# schematic.net
KiCad netlist of a schematic drawn in EAGLE
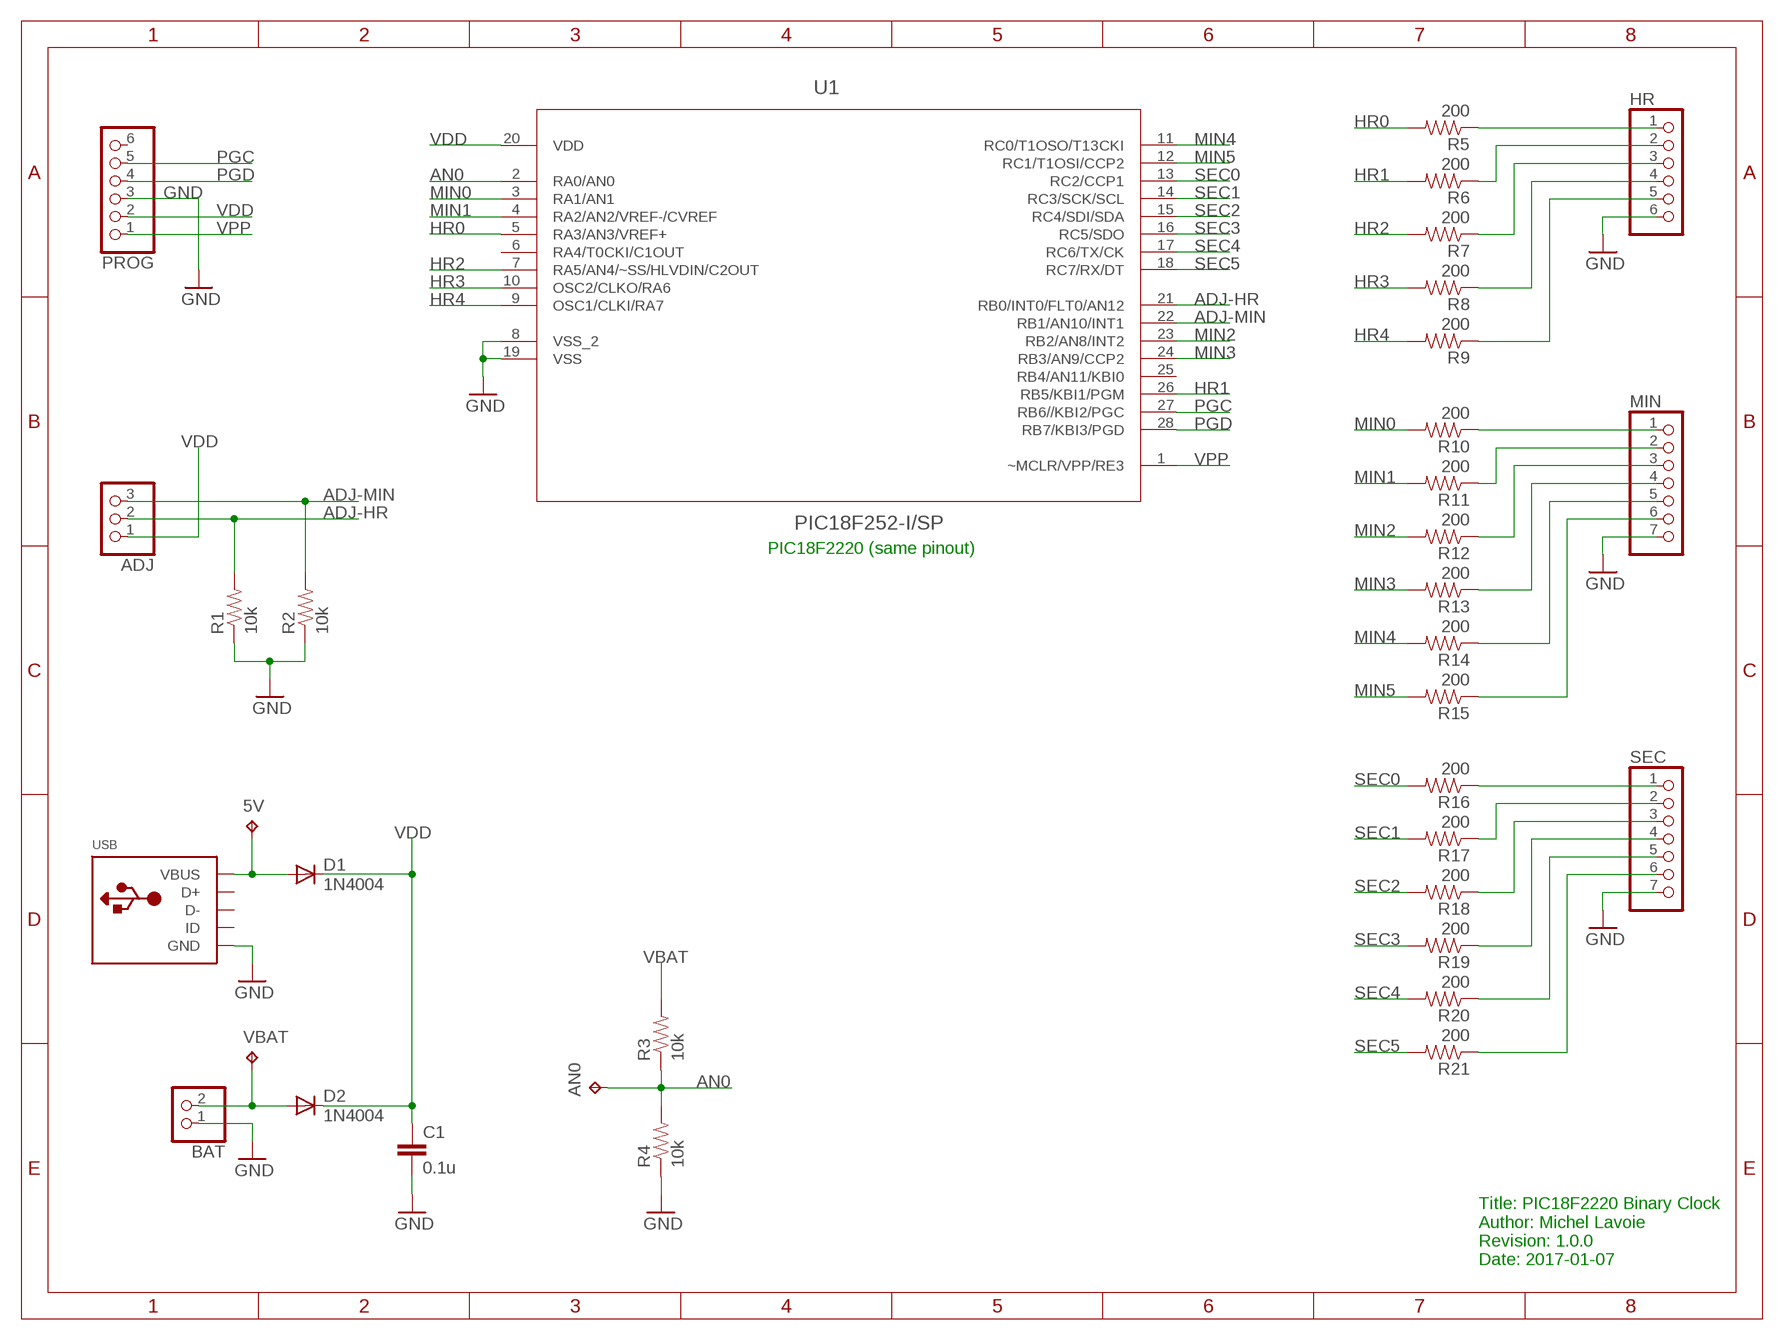
[diagram p0: schematic, sheet 1]

(export (version "E")
  (design (tool "Eeschema 10.0.6"))
  (components
    (comp (ref "5V")
      (value "TPPAD1-13")
      (footprint "eagle-import:P1-13")
      (libsource (lib "eagle-import") (part "TPPAD1-13"))
    )
    (comp (ref "ADJ")
      (value "PINHD-1X3")
      (footprint "eagle-import:1X03")
      (libsource (lib "eagle-import") (part "PINHD-1X3"))
    )
    (comp (ref "AN0")
      (value "TPPAD1-13")
      (footprint "eagle-import:P1-13")
      (libsource (lib "eagle-import") (part "TPPAD1-13"))
    )
    (comp (ref "BAT")
      (value "PINHD-1X2")
      (footprint "eagle-import:1X02")
      (libsource (lib "eagle-import") (part "PINHD-1X2"))
    )
    (comp (ref "C1")
      (value "0.1u")
      (footprint "eagle-import:CAP-PTH-SMALL-KIT")
      (libsource (lib "eagle-import") (part "0.1UF-50V-20%(PTH)KIT-EZ"))
    )
    (comp (ref "D1")
      (value "1N4004")
      (footprint "eagle-import:DO41-10")
      (libsource (lib "eagle-import") (part "1N4004"))
    )
    (comp (ref "D2")
      (value "1N4004")
      (footprint "eagle-import:DO41-10")
      (libsource (lib "eagle-import") (part "1N4004"))
    )
    (comp (ref "HR")
      (value "PINHD-1X6")
      (footprint "eagle-import:1X06")
      (libsource (lib "eagle-import") (part "PINHD-1X6"))
    )
    (comp (ref "MIN")
      (value "PINHD-1X7")
      (footprint "eagle-import:1X07")
      (libsource (lib "eagle-import") (part "PINHD-1X7"))
    )
    (comp (ref "PROG")
      (value "PINHD-1X6")
      (footprint "eagle-import:1X06")
      (libsource (lib "eagle-import") (part "PINHD-1X6"))
    )
    (comp (ref "R1")
      (value "10k")
      (footprint "eagle-import:AXIAL-0.3")
      (libsource (lib "eagle-import") (part "10KOHM-1/4W5%(PTH)"))
    )
    (comp (ref "R2")
      (value "10k")
      (footprint "eagle-import:AXIAL-0.3")
      (libsource (lib "eagle-import") (part "10KOHM-1/4W5%(PTH)"))
    )
    (comp (ref "R3")
      (value "10k")
      (footprint "eagle-import:AXIAL-0.3")
      (libsource (lib "eagle-import") (part "10KOHM-1/4W5%(PTH)"))
    )
    (comp (ref "R4")
      (value "10k")
      (footprint "eagle-import:AXIAL-0.3")
      (libsource (lib "eagle-import") (part "10KOHM-1/4W5%(PTH)"))
    )
    (comp (ref "R5")
      (value "200")
      (footprint "eagle-import:AXIAL-0.3")
      (libsource (lib "eagle-import") (part "10KOHM-1/4W5%(PTH)"))
    )
    (comp (ref "R6")
      (value "200")
      (footprint "eagle-import:AXIAL-0.3")
      (libsource (lib "eagle-import") (part "10KOHM-1/4W5%(PTH)"))
    )
    (comp (ref "R7")
      (value "200")
      (footprint "eagle-import:AXIAL-0.3")
      (libsource (lib "eagle-import") (part "10KOHM-1/4W5%(PTH)"))
    )
    (comp (ref "R8")
      (value "200")
      (footprint "eagle-import:AXIAL-0.3")
      (libsource (lib "eagle-import") (part "10KOHM-1/4W5%(PTH)"))
    )
    (comp (ref "R9")
      (value "200")
      (footprint "eagle-import:AXIAL-0.3")
      (libsource (lib "eagle-import") (part "10KOHM-1/4W5%(PTH)"))
    )
    (comp (ref "R10")
      (value "200")
      (footprint "eagle-import:AXIAL-0.3")
      (libsource (lib "eagle-import") (part "10KOHM-1/4W5%(PTH)"))
    )
    (comp (ref "R11")
      (value "200")
      (footprint "eagle-import:AXIAL-0.3")
      (libsource (lib "eagle-import") (part "10KOHM-1/4W5%(PTH)"))
    )
    (comp (ref "R12")
      (value "200")
      (footprint "eagle-import:AXIAL-0.3")
      (libsource (lib "eagle-import") (part "10KOHM-1/4W5%(PTH)"))
    )
    (comp (ref "R13")
      (value "200")
      (footprint "eagle-import:AXIAL-0.3")
      (libsource (lib "eagle-import") (part "10KOHM-1/4W5%(PTH)"))
    )
    (comp (ref "R14")
      (value "200")
      (footprint "eagle-import:AXIAL-0.3")
      (libsource (lib "eagle-import") (part "10KOHM-1/4W5%(PTH)"))
    )
    (comp (ref "R15")
      (value "200")
      (footprint "eagle-import:AXIAL-0.3")
      (libsource (lib "eagle-import") (part "10KOHM-1/4W5%(PTH)"))
    )
    (comp (ref "R16")
      (value "200")
      (footprint "eagle-import:AXIAL-0.3")
      (libsource (lib "eagle-import") (part "10KOHM-1/4W5%(PTH)"))
    )
    (comp (ref "R17")
      (value "200")
      (footprint "eagle-import:AXIAL-0.3")
      (libsource (lib "eagle-import") (part "10KOHM-1/4W5%(PTH)"))
    )
    (comp (ref "R18")
      (value "200")
      (footprint "eagle-import:AXIAL-0.3")
      (libsource (lib "eagle-import") (part "10KOHM-1/4W5%(PTH)"))
    )
    (comp (ref "R19")
      (value "200")
      (footprint "eagle-import:AXIAL-0.3")
      (libsource (lib "eagle-import") (part "10KOHM-1/4W5%(PTH)"))
    )
    (comp (ref "R20")
      (value "200")
      (footprint "eagle-import:AXIAL-0.3")
      (libsource (lib "eagle-import") (part "10KOHM-1/4W5%(PTH)"))
    )
    (comp (ref "R21")
      (value "200")
      (footprint "eagle-import:AXIAL-0.3")
      (libsource (lib "eagle-import") (part "10KOHM-1/4W5%(PTH)"))
    )
    (comp (ref "SEC")
      (value "PINHD-1X7")
      (footprint "eagle-import:1X07")
      (libsource (lib "eagle-import") (part "PINHD-1X7"))
    )
    (comp (ref "U1")
      (value "PIC18F252-I/SP")
      (footprint "eagle-import:DIP254P762X508-28")
      (libsource (lib "eagle-import") (part "PIC18F252-I/SP"))
    )
    (comp (ref "USB")
      (value "USBTHM")
      (footprint "eagle-import:USB-MINIB-THM")
      (libsource (lib "eagle-import") (part "USBTHM"))
    )
    (comp (ref "VBAT")
      (value "TPPAD1-13")
      (footprint "eagle-import:P1-13")
      (libsource (lib "eagle-import") (part "TPPAD1-13"))
    )
  )
  (nets
    (net (code "1") (name "/ADJ-HR") (class "Default")
      (node (ref "ADJ") (pin "2") (pinfunction "2_2") (pintype "passive"))
      (node (ref "R1") (pin "P$2") (pinfunction "2_P$2") (pintype "passive"))
      (node (ref "U1") (pin "21") (pinfunction "RB0/INT0/FLT0/AN12_21") (pintype "bidirectional"))
    )
    (net (code "2") (name "/ADJ-MIN") (class "Default")
      (node (ref "ADJ") (pin "3") (pinfunction "3_3") (pintype "passive"))
      (node (ref "R2") (pin "P$2") (pinfunction "2_P$2") (pintype "passive"))
      (node (ref "U1") (pin "22") (pinfunction "RB1/AN10/INT1_22") (pintype "bidirectional"))
    )
    (net (code "3") (name "/AN0") (class "Default")
      (node (ref "AN0") (pin "TP") (pinfunction "TP_TP") (pintype "input"))
      (node (ref "R3") (pin "P$1") (pinfunction "1_P$1") (pintype "passive"))
      (node (ref "R4") (pin "P$2") (pinfunction "2_P$2") (pintype "passive"))
      (node (ref "U1") (pin "2") (pinfunction "RA0/AN0_2") (pintype "bidirectional"))
    )
    (net (code "4") (name "/HR0") (class "Default")
      (node (ref "R5") (pin "P$2") (pinfunction "2_P$2") (pintype "passive"))
      (node (ref "U1") (pin "5") (pinfunction "RA3/AN3/VREF+_5") (pintype "bidirectional"))
    )
    (net (code "5") (name "/HR1") (class "Default")
      (node (ref "R6") (pin "P$2") (pinfunction "2_P$2") (pintype "passive"))
      (node (ref "U1") (pin "26") (pinfunction "RB5/KBI1/PGM_26") (pintype "bidirectional"))
    )
    (net (code "6") (name "/HR2") (class "Default")
      (node (ref "R7") (pin "P$2") (pinfunction "2_P$2") (pintype "passive"))
      (node (ref "U1") (pin "7") (pinfunction "RA5/AN4/~{SS/HLVDIN/C2OUT}_7") (pintype "bidirectional"))
    )
    (net (code "7") (name "/HR3") (class "Default")
      (node (ref "R8") (pin "P$2") (pinfunction "2_P$2") (pintype "passive"))
      (node (ref "U1") (pin "10") (pinfunction "OSC2/CLKO/RA6_10") (pintype "bidirectional"))
    )
    (net (code "8") (name "/HR4") (class "Default")
      (node (ref "R9") (pin "P$2") (pinfunction "2_P$2") (pintype "passive"))
      (node (ref "U1") (pin "9") (pinfunction "OSC1/CLKI/RA7_9") (pintype "bidirectional"))
    )
    (net (code "9") (name "/MIN0") (class "Default")
      (node (ref "R10") (pin "P$2") (pinfunction "2_P$2") (pintype "passive"))
      (node (ref "U1") (pin "3") (pinfunction "RA1/AN1_3") (pintype "bidirectional"))
    )
    (net (code "10") (name "/MIN1") (class "Default")
      (node (ref "R11") (pin "P$2") (pinfunction "2_P$2") (pintype "passive"))
      (node (ref "U1") (pin "4") (pinfunction "RA2/AN2/VREF-/CVREF_4") (pintype "bidirectional"))
    )
    (net (code "11") (name "/MIN2") (class "Default")
      (node (ref "R12") (pin "P$2") (pinfunction "2_P$2") (pintype "passive"))
      (node (ref "U1") (pin "23") (pinfunction "RB2/AN8/INT2_23") (pintype "bidirectional"))
    )
    (net (code "12") (name "/MIN3") (class "Default")
      (node (ref "R13") (pin "P$2") (pinfunction "2_P$2") (pintype "passive"))
      (node (ref "U1") (pin "24") (pinfunction "RB3/AN9/CCP2_24") (pintype "bidirectional"))
    )
    (net (code "13") (name "/MIN4") (class "Default")
      (node (ref "R14") (pin "P$2") (pinfunction "2_P$2") (pintype "passive"))
      (node (ref "U1") (pin "11") (pinfunction "RC0/T1OSO/T13CKI_11") (pintype "bidirectional"))
    )
    (net (code "14") (name "/MIN5") (class "Default")
      (node (ref "R15") (pin "P$2") (pinfunction "2_P$2") (pintype "passive"))
      (node (ref "U1") (pin "12") (pinfunction "RC1/T1OSI/CCP2_12") (pintype "bidirectional"))
    )
    (net (code "15") (name "/PGC") (class "Default")
      (node (ref "PROG") (pin "5") (pinfunction "5_5") (pintype "passive"))
      (node (ref "U1") (pin "27") (pinfunction "RB6//KBI2/PGC_27") (pintype "bidirectional"))
    )
    (net (code "16") (name "/PGD") (class "Default")
      (node (ref "PROG") (pin "4") (pinfunction "4_4") (pintype "passive"))
      (node (ref "U1") (pin "28") (pinfunction "RB7/KBI3/PGD_28") (pintype "bidirectional"))
    )
    (net (code "17") (name "/SEC0") (class "Default")
      (node (ref "R16") (pin "P$2") (pinfunction "2_P$2") (pintype "passive"))
      (node (ref "U1") (pin "13") (pinfunction "RC2/CCP1_13") (pintype "bidirectional"))
    )
    (net (code "18") (name "/SEC1") (class "Default")
      (node (ref "R17") (pin "P$2") (pinfunction "2_P$2") (pintype "passive"))
      (node (ref "U1") (pin "14") (pinfunction "RC3/SCK/SCL_14") (pintype "bidirectional"))
    )
    (net (code "19") (name "/SEC2") (class "Default")
      (node (ref "R18") (pin "P$2") (pinfunction "2_P$2") (pintype "passive"))
      (node (ref "U1") (pin "15") (pinfunction "RC4/SDI/SDA_15") (pintype "bidirectional"))
    )
    (net (code "20") (name "/SEC3") (class "Default")
      (node (ref "R19") (pin "P$2") (pinfunction "2_P$2") (pintype "passive"))
      (node (ref "U1") (pin "16") (pinfunction "RC5/SDO_16") (pintype "bidirectional"))
    )
    (net (code "21") (name "/SEC4") (class "Default")
      (node (ref "R20") (pin "P$2") (pinfunction "2_P$2") (pintype "passive"))
      (node (ref "U1") (pin "17") (pinfunction "RC6/TX/CK_17") (pintype "bidirectional"))
    )
    (net (code "22") (name "/SEC5") (class "Default")
      (node (ref "R21") (pin "P$2") (pinfunction "2_P$2") (pintype "passive"))
      (node (ref "U1") (pin "18") (pinfunction "RC7/RX/DT_18") (pintype "bidirectional"))
    )
    (net (code "23") (name "/VBAT") (class "Default")
      (node (ref "BAT") (pin "2") (pinfunction "2_2") (pintype "passive"))
      (node (ref "D2") (pin "A") (pinfunction "A_A") (pintype "passive"))
      (node (ref "R3") (pin "P$2") (pinfunction "2_P$2") (pintype "passive"))
      (node (ref "VBAT") (pin "TP") (pinfunction "TP_TP") (pintype "input"))
    )
    (net (code "24") (name "/VDD") (class "Default")
      (node (ref "ADJ") (pin "1") (pinfunction "1_1") (pintype "passive"))
      (node (ref "C1") (pin "1") (pinfunction "1_1") (pintype "passive"))
      (node (ref "D1") (pin "C") (pinfunction "C_C") (pintype "passive"))
      (node (ref "D2") (pin "C") (pinfunction "C_C") (pintype "passive"))
      (node (ref "PROG") (pin "2") (pinfunction "2_2") (pintype "passive"))
      (node (ref "U1") (pin "20") (pinfunction "VDD_20") (pintype "power_in"))
    )
    (net (code "25") (name "/VPP") (class "Default")
      (node (ref "PROG") (pin "1") (pinfunction "1_1") (pintype "passive"))
      (node (ref "U1") (pin "1") (pinfunction "~{MCLR/VPP/RE3}_1") (pintype "bidirectional"))
    )
    (net (code "26") (name "GND") (class "Default")
      (node (ref "BAT") (pin "1") (pinfunction "1_1") (pintype "passive"))
      (node (ref "C1") (pin "2") (pinfunction "2_2") (pintype "passive"))
      (node (ref "HR") (pin "6") (pinfunction "6_6") (pintype "passive"))
      (node (ref "MIN") (pin "7") (pinfunction "7_7") (pintype "passive"))
      (node (ref "PROG") (pin "3") (pinfunction "3_3") (pintype "passive"))
      (node (ref "R1") (pin "P$1") (pinfunction "1_P$1") (pintype "passive"))
      (node (ref "R2") (pin "P$1") (pinfunction "1_P$1") (pintype "passive"))
      (node (ref "R4") (pin "P$1") (pinfunction "1_P$1") (pintype "passive"))
      (node (ref "SEC") (pin "7") (pinfunction "7_7") (pintype "passive"))
      (node (ref "U1") (pin "19") (pinfunction "VSS_19") (pintype "power_in"))
      (node (ref "U1") (pin "8") (pinfunction "VSS_2_8") (pintype "power_in"))
      (node (ref "USB") (pin "GND") (pinfunction "GND_GND") (pintype "power_in"))
    )
    (net (code "27") (name "Net-(5V-PadTP)") (class "Default")
      (node (ref "5V") (pin "TP") (pinfunction "TP_TP") (pintype "input"))
      (node (ref "D1") (pin "A") (pinfunction "A_A") (pintype "passive"))
      (node (ref "USB") (pin "VBUS") (pinfunction "VBUS_VBUS") (pintype "power_in"))
    )
    (net (code "28") (name "Net-(R5-1)") (class "Default")
      (node (ref "HR") (pin "1") (pinfunction "1_1") (pintype "passive"))
      (node (ref "R5") (pin "P$1") (pinfunction "1_P$1") (pintype "passive"))
    )
    (net (code "29") (name "Net-(R6-1)") (class "Default")
      (node (ref "HR") (pin "2") (pinfunction "2_2") (pintype "passive"))
      (node (ref "R6") (pin "P$1") (pinfunction "1_P$1") (pintype "passive"))
    )
    (net (code "30") (name "Net-(R7-1)") (class "Default")
      (node (ref "HR") (pin "3") (pinfunction "3_3") (pintype "passive"))
      (node (ref "R7") (pin "P$1") (pinfunction "1_P$1") (pintype "passive"))
    )
    (net (code "31") (name "Net-(R8-1)") (class "Default")
      (node (ref "HR") (pin "4") (pinfunction "4_4") (pintype "passive"))
      (node (ref "R8") (pin "P$1") (pinfunction "1_P$1") (pintype "passive"))
    )
    (net (code "32") (name "Net-(R9-1)") (class "Default")
      (node (ref "HR") (pin "5") (pinfunction "5_5") (pintype "passive"))
      (node (ref "R9") (pin "P$1") (pinfunction "1_P$1") (pintype "passive"))
    )
    (net (code "33") (name "Net-(R10-1)") (class "Default")
      (node (ref "MIN") (pin "1") (pinfunction "1_1") (pintype "passive"))
      (node (ref "R10") (pin "P$1") (pinfunction "1_P$1") (pintype "passive"))
    )
    (net (code "34") (name "Net-(R11-1)") (class "Default")
      (node (ref "MIN") (pin "2") (pinfunction "2_2") (pintype "passive"))
      (node (ref "R11") (pin "P$1") (pinfunction "1_P$1") (pintype "passive"))
    )
    (net (code "35") (name "Net-(R12-1)") (class "Default")
      (node (ref "MIN") (pin "3") (pinfunction "3_3") (pintype "passive"))
      (node (ref "R12") (pin "P$1") (pinfunction "1_P$1") (pintype "passive"))
    )
    (net (code "36") (name "Net-(R13-1)") (class "Default")
      (node (ref "MIN") (pin "4") (pinfunction "4_4") (pintype "passive"))
      (node (ref "R13") (pin "P$1") (pinfunction "1_P$1") (pintype "passive"))
    )
    (net (code "37") (name "Net-(R14-1)") (class "Default")
      (node (ref "MIN") (pin "5") (pinfunction "5_5") (pintype "passive"))
      (node (ref "R14") (pin "P$1") (pinfunction "1_P$1") (pintype "passive"))
    )
    (net (code "38") (name "Net-(R15-1)") (class "Default")
      (node (ref "MIN") (pin "6") (pinfunction "6_6") (pintype "passive"))
      (node (ref "R15") (pin "P$1") (pinfunction "1_P$1") (pintype "passive"))
    )
    (net (code "39") (name "Net-(R16-1)") (class "Default")
      (node (ref "R16") (pin "P$1") (pinfunction "1_P$1") (pintype "passive"))
      (node (ref "SEC") (pin "1") (pinfunction "1_1") (pintype "passive"))
    )
    (net (code "40") (name "Net-(R17-1)") (class "Default")
      (node (ref "R17") (pin "P$1") (pinfunction "1_P$1") (pintype "passive"))
      (node (ref "SEC") (pin "2") (pinfunction "2_2") (pintype "passive"))
    )
    (net (code "41") (name "Net-(R18-1)") (class "Default")
      (node (ref "R18") (pin "P$1") (pinfunction "1_P$1") (pintype "passive"))
      (node (ref "SEC") (pin "3") (pinfunction "3_3") (pintype "passive"))
    )
    (net (code "42") (name "Net-(R19-1)") (class "Default")
      (node (ref "R19") (pin "P$1") (pinfunction "1_P$1") (pintype "passive"))
      (node (ref "SEC") (pin "4") (pinfunction "4_4") (pintype "passive"))
    )
    (net (code "43") (name "Net-(R20-1)") (class "Default")
      (node (ref "R20") (pin "P$1") (pinfunction "1_P$1") (pintype "passive"))
      (node (ref "SEC") (pin "5") (pinfunction "5_5") (pintype "passive"))
    )
    (net (code "44") (name "Net-(R21-1)") (class "Default")
      (node (ref "R21") (pin "P$1") (pinfunction "1_P$1") (pintype "passive"))
      (node (ref "SEC") (pin "6") (pinfunction "6_6") (pintype "passive"))
    )
    (net (code "45") (name "unconnected-(PROG-Pad6)") (class "Default")
      (node (ref "PROG") (pin "6") (pinfunction "6_6") (pintype "passive"))
    )
    (net (code "46") (name "unconnected-(U1-RA4{slash}T0CKI{slash}C1OUT-Pad6)") (class "Default")
      (node (ref "U1") (pin "6") (pinfunction "RA4/T0CKI/C1OUT_6") (pintype "bidirectional"))
    )
    (net (code "47") (name "unconnected-(U1-RB4{slash}AN11{slash}KBI0-Pad25)") (class "Default")
      (node (ref "U1") (pin "25") (pinfunction "RB4/AN11/KBI0_25") (pintype "bidirectional"))
    )
    (net (code "48") (name "unconnected-(USB-PadD+)") (class "Default")
      (node (ref "USB") (pin "D+") (pinfunction "D+_D+") (pintype "bidirectional"))
    )
    (net (code "49") (name "unconnected-(USB-PadD-)") (class "Default")
      (node (ref "USB") (pin "D-") (pinfunction "D-_D-") (pintype "bidirectional"))
    )
    (net (code "50") (name "unconnected-(USB-PadID)") (class "Default")
      (node (ref "USB") (pin "ID") (pinfunction "ID_ID") (pintype "bidirectional"))
    )
  )
)
